# SensorTesting.net
KiCad netlist of a schematic drawn in EAGLE
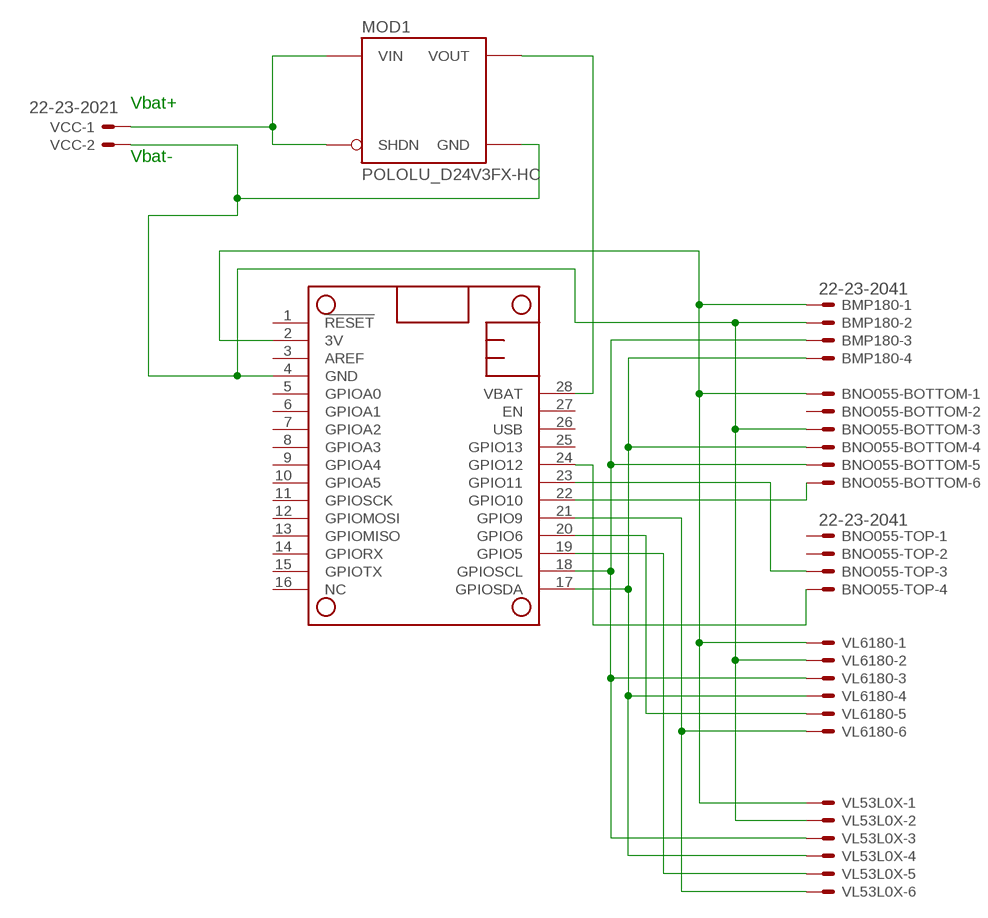
[diagram p0: schematic, sheet 1]

(export (version "E")
  (design (tool "Eeschema 10.0.6"))
  (components
    (comp (ref "BMP180")
      (value "22-23-2041")
      (footprint "eagle-import:22-23-2041")
      (fields (field (name "MF") "MOLEX"))
      (libsource (lib "eagle-import") (part "22-23-2041"))
    )
    (comp (ref "BNO055-BOTTOM")
      (value "22-23-2061")
      (footprint "eagle-import:22-23-2061")
      (fields (field (name "MF") "MOLEX"))
      (libsource (lib "eagle-import") (part "22-23-2061"))
    )
    (comp (ref "BNO055-TOP")
      (value "22-23-2041")
      (footprint "eagle-import:22-23-2041")
      (fields (field (name "MF") "MOLEX"))
      (libsource (lib "eagle-import") (part "22-23-2041"))
    )
    (comp (ref "MOD1")
      (value "POLOLU_D24V3FX-HC")
      (footprint "eagle-import:POLOLU_D24V3F_HC")
      (libsource (lib "eagle-import") (part "POLOLU_D24V3F-HCX"))
    )
    (comp (ref "MS1")
      (value "FEATHERWING_NODIM")
      (footprint "eagle-import:FEATHERWING_DIM")
      (libsource (lib "eagle-import") (part "FEATHERWING_NODIM"))
    )
    (comp (ref "VCC")
      (value "22-23-2021")
      (footprint "eagle-import:22-23-2021")
      (fields (field (name "MF") "MOLEX"))
      (libsource (lib "eagle-import") (part "22-23-2021"))
    )
    (comp (ref "VL53L0X")
      (value "22-23-2061")
      (footprint "eagle-import:22-23-2061")
      (fields (field (name "MF") "MOLEX"))
      (libsource (lib "eagle-import") (part "22-23-2061"))
    )
    (comp (ref "VL6180")
      (value "22-23-2061")
      (footprint "eagle-import:22-23-2061")
      (fields (field (name "MF") "MOLEX"))
      (libsource (lib "eagle-import") (part "22-23-2061"))
    )
  )
  (nets
    (net (code "1") (name "/USB") (class "Default")
      (node (ref "MS1") (pin "26") (pinfunction "USB_26") (pintype "power_in"))
    )
    (net (code "2") (name "Net-(BMP180A-S)") (class "Default")
      (node (ref "BMP180") (pin "1") (pinfunction "S_1") (pintype "passive"))
      (node (ref "BNO055-BOTTOM") (pin "1") (pinfunction "S_1") (pintype "passive"))
      (node (ref "MS1") (pin "2") (pinfunction "3V_2") (pintype "power_in"))
      (node (ref "VL53L0X") (pin "1") (pinfunction "S_1") (pintype "passive"))
      (node (ref "VL6180") (pin "1") (pinfunction "S_1") (pintype "passive"))
    )
    (net (code "3") (name "Net-(BMP180B-S)") (class "Default")
      (node (ref "BMP180") (pin "2") (pinfunction "S_2") (pintype "passive"))
      (node (ref "BNO055-BOTTOM") (pin "3") (pinfunction "S_3") (pintype "passive"))
      (node (ref "MOD1") (pin "G") (pinfunction "GND_G") (pintype "power_in"))
      (node (ref "MS1") (pin "4") (pinfunction "GND_4") (pintype "power_in"))
      (node (ref "VCC") (pin "2") (pinfunction "S_2") (pintype "passive"))
      (node (ref "VL53L0X") (pin "2") (pinfunction "S_2") (pintype "passive"))
      (node (ref "VL6180") (pin "2") (pinfunction "S_2") (pintype "passive"))
    )
    (net (code "4") (name "Net-(BMP180C-S)") (class "Default")
      (node (ref "BMP180") (pin "3") (pinfunction "S_3") (pintype "passive"))
      (node (ref "BNO055-BOTTOM") (pin "5") (pinfunction "S_5") (pintype "passive"))
      (node (ref "MS1") (pin "18") (pinfunction "GPIOSCL_18") (pintype "bidirectional"))
      (node (ref "VL53L0X") (pin "3") (pinfunction "S_3") (pintype "passive"))
      (node (ref "VL6180") (pin "3") (pinfunction "S_3") (pintype "passive"))
    )
    (net (code "5") (name "Net-(BMP180D-S)") (class "Default")
      (node (ref "BMP180") (pin "4") (pinfunction "S_4") (pintype "passive"))
      (node (ref "BNO055-BOTTOM") (pin "4") (pinfunction "S_4") (pintype "passive"))
      (node (ref "MS1") (pin "17") (pinfunction "GPIOSDA_17") (pintype "bidirectional"))
      (node (ref "VL53L0X") (pin "4") (pinfunction "S_4") (pintype "passive"))
      (node (ref "VL6180") (pin "4") (pinfunction "S_4") (pintype "passive"))
    )
    (net (code "6") (name "Net-(BNO055-BOTTOMF-S)") (class "Default")
      (node (ref "BNO055-BOTTOM") (pin "6") (pinfunction "S_6") (pintype "passive"))
      (node (ref "MS1") (pin "22") (pinfunction "GPIO10_22") (pintype "bidirectional"))
    )
    (net (code "7") (name "Net-(BNO055-TOPC-S)") (class "Default")
      (node (ref "BNO055-TOP") (pin "3") (pinfunction "S_3") (pintype "passive"))
      (node (ref "MS1") (pin "23") (pinfunction "GPIO11_23") (pintype "bidirectional"))
    )
    (net (code "8") (name "Net-(BNO055-TOPD-S)") (class "Default")
      (node (ref "BNO055-TOP") (pin "4") (pinfunction "S_4") (pintype "passive"))
      (node (ref "MS1") (pin "24") (pinfunction "GPIO12_24") (pintype "bidirectional"))
    )
    (net (code "9") (name "Net-(MOD1-SHDN)") (class "Default")
      (node (ref "MOD1") (pin "I") (pinfunction "VIN_I") (pintype "power_in"))
      (node (ref "MOD1") (pin "S") (pinfunction "SHDN_S") (pintype "input"))
      (node (ref "VCC") (pin "1") (pinfunction "S_1") (pintype "passive"))
    )
    (net (code "10") (name "Net-(MOD1-VOUT)") (class "Default")
      (node (ref "MOD1") (pin "O") (pinfunction "VOUT_O") (pintype "output"))
      (node (ref "MS1") (pin "28") (pinfunction "VBAT_28") (pintype "power_in"))
    )
    (net (code "11") (name "Net-(MS1-GPIO5)") (class "Default")
      (node (ref "MS1") (pin "19") (pinfunction "GPIO5_19") (pintype "bidirectional"))
      (node (ref "VL53L0X") (pin "5") (pinfunction "S_5") (pintype "passive"))
    )
    (net (code "12") (name "Net-(MS1-GPIO6)") (class "Default")
      (node (ref "MS1") (pin "20") (pinfunction "GPIO6_20") (pintype "bidirectional"))
      (node (ref "VL6180") (pin "5") (pinfunction "S_5") (pintype "passive"))
    )
    (net (code "13") (name "Net-(MS1-GPIO9)") (class "Default")
      (node (ref "MS1") (pin "21") (pinfunction "GPIO9_21") (pintype "bidirectional"))
      (node (ref "VL53L0X") (pin "6") (pinfunction "S_6") (pintype "passive"))
      (node (ref "VL6180") (pin "6") (pinfunction "S_6") (pintype "passive"))
    )
    (net (code "14") (name "unconnected-(BNO055-BOTTOMB-S-Pad2)") (class "Default")
      (node (ref "BNO055-BOTTOM") (pin "2") (pinfunction "S_2") (pintype "passive"))
    )
    (net (code "15") (name "unconnected-(BNO055-TOPA-S-Pad1)") (class "Default")
      (node (ref "BNO055-TOP") (pin "1") (pinfunction "S_1") (pintype "passive"))
    )
    (net (code "16") (name "unconnected-(BNO055-TOPB-S-Pad2)") (class "Default")
      (node (ref "BNO055-TOP") (pin "2") (pinfunction "S_2") (pintype "passive"))
    )
    (net (code "17") (name "unconnected-(MS1-AREF-Pad3)") (class "Default")
      (node (ref "MS1") (pin "3") (pinfunction "AREF_3") (pintype "passive"))
    )
    (net (code "18") (name "unconnected-(MS1-EN-Pad27)") (class "Default")
      (node (ref "MS1") (pin "27") (pinfunction "EN_27") (pintype "passive"))
    )
    (net (code "19") (name "unconnected-(MS1-GPIO13-Pad25)") (class "Default")
      (node (ref "MS1") (pin "25") (pinfunction "GPIO13_25") (pintype "bidirectional"))
    )
    (net (code "20") (name "unconnected-(MS1-GPIOA0-Pad5)") (class "Default")
      (node (ref "MS1") (pin "5") (pinfunction "GPIOA0_5") (pintype "bidirectional"))
    )
    (net (code "21") (name "unconnected-(MS1-GPIOA1-Pad6)") (class "Default")
      (node (ref "MS1") (pin "6") (pinfunction "GPIOA1_6") (pintype "bidirectional"))
    )
    (net (code "22") (name "unconnected-(MS1-GPIOA2-Pad7)") (class "Default")
      (node (ref "MS1") (pin "7") (pinfunction "GPIOA2_7") (pintype "bidirectional"))
    )
    (net (code "23") (name "unconnected-(MS1-GPIOA3-Pad8)") (class "Default")
      (node (ref "MS1") (pin "8") (pinfunction "GPIOA3_8") (pintype "bidirectional"))
    )
    (net (code "24") (name "unconnected-(MS1-GPIOA4-Pad9)") (class "Default")
      (node (ref "MS1") (pin "9") (pinfunction "GPIOA4_9") (pintype "bidirectional"))
    )
    (net (code "25") (name "unconnected-(MS1-GPIOA5-Pad10)") (class "Default")
      (node (ref "MS1") (pin "10") (pinfunction "GPIOA5_10") (pintype "bidirectional"))
    )
    (net (code "26") (name "unconnected-(MS1-GPIOMISO-Pad13)") (class "Default")
      (node (ref "MS1") (pin "13") (pinfunction "GPIOMISO_13") (pintype "bidirectional"))
    )
    (net (code "27") (name "unconnected-(MS1-GPIOMOSI-Pad12)") (class "Default")
      (node (ref "MS1") (pin "12") (pinfunction "GPIOMOSI_12") (pintype "bidirectional"))
    )
    (net (code "28") (name "unconnected-(MS1-GPIORX-Pad14)") (class "Default")
      (node (ref "MS1") (pin "14") (pinfunction "GPIORX_14") (pintype "bidirectional"))
    )
    (net (code "29") (name "unconnected-(MS1-GPIOSCK-Pad11)") (class "Default")
      (node (ref "MS1") (pin "11") (pinfunction "GPIOSCK_11") (pintype "bidirectional"))
    )
    (net (code "30") (name "unconnected-(MS1-GPIOTX-Pad15)") (class "Default")
      (node (ref "MS1") (pin "15") (pinfunction "GPIOTX_15") (pintype "bidirectional"))
    )
    (net (code "31") (name "unconnected-(MS1-NC-Pad16)") (class "Default")
      (node (ref "MS1") (pin "16") (pinfunction "NC_16") (pintype "passive"))
    )
    (net (code "32") (name "unconnected-(MS1-~{RESET}-Pad1)") (class "Default")
      (node (ref "MS1") (pin "1") (pinfunction "~{RESET}_1") (pintype "input"))
    )
  )
)
